# ProPrj_CC-board_2026-02-09.net
KiCad netlist of a schematic drawn in EasyEDA Pro
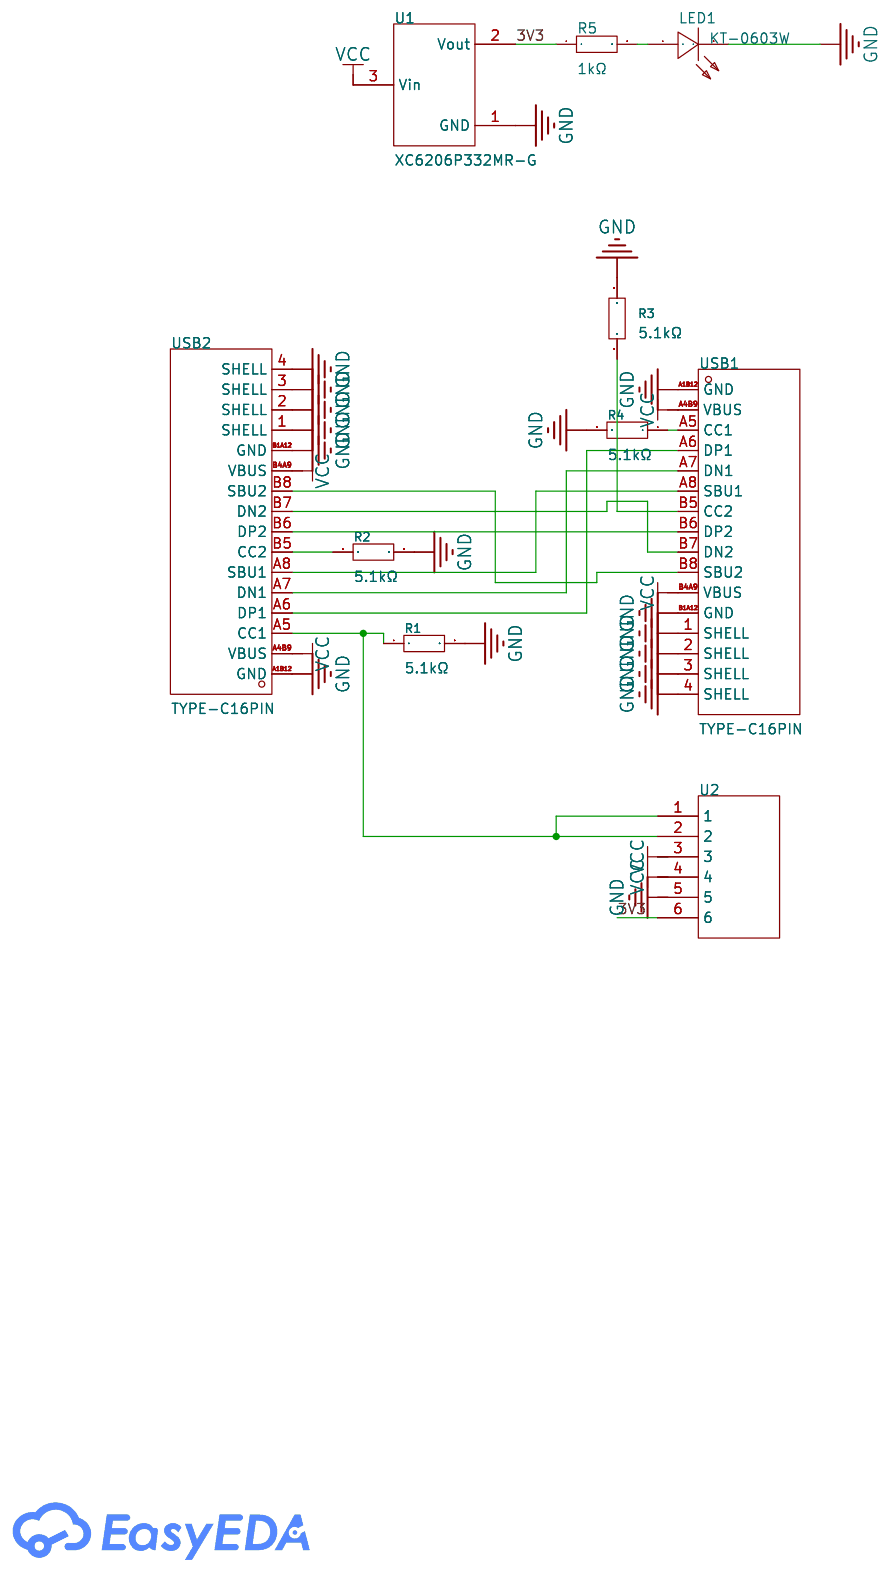
[diagram p0: schematic sheet]

(export (version "E")
  (design (tool "Eeschema 10.0.6"))
  (components
    (comp (ref "LED1")
      (value "KT-0603W")
      (footprint "easyedapro:LED0603-R-RD_WHITE")
      (fields (field (name "Manufacturer") "KENTO"))
      (libsource (lib "easyedapro") (part "0603White light_C2290"))
    )
    (comp (ref "R1")
      (value "5.1kΩ")
      (footprint "easyedapro:R0402")
      (fields
        (field (name "Manufacturer Part") "0402WGF5101TCE")
        (field (name "Manufacturer") "UNI-ROYAL(厚声)")
      )
      (libsource (lib "easyedapro") (part "0402WGF5101TCE"))
    )
    (comp (ref "R2")
      (value "5.1kΩ")
      (footprint "easyedapro:R0402")
      (fields
        (field (name "Manufacturer Part") "0402WGF5101TCE")
        (field (name "Manufacturer") "UNI-ROYAL(厚声)")
      )
      (libsource (lib "easyedapro") (part "0402WGF5101TCE"))
    )
    (comp (ref "R3")
      (value "5.1kΩ")
      (footprint "easyedapro:R0402")
      (fields
        (field (name "Manufacturer Part") "0402WGF5101TCE")
        (field (name "Manufacturer") "UNI-ROYAL(厚声)")
      )
      (libsource (lib "easyedapro") (part "0402WGF5101TCE"))
    )
    (comp (ref "R4")
      (value "5.1kΩ")
      (footprint "easyedapro:R0402")
      (fields
        (field (name "Manufacturer Part") "0402WGF5101TCE")
        (field (name "Manufacturer") "UNI-ROYAL(厚声)")
      )
      (libsource (lib "easyedapro") (part "0402WGF5101TCE"))
    )
    (comp (ref "R5")
      (value "1kΩ")
      (footprint "easyedapro:R0402")
      (fields
        (field (name "Manufacturer Part") "0402WGF1001TCE")
        (field (name "Manufacturer") "UNI-ROYAL(厚声)")
      )
      (libsource (lib "easyedapro") (part "0402WGF1001TCE"))
    )
    (comp (ref "U1")
      (value "XC6206P332MR-G")
      (footprint "easyedapro:SOT-23-3_L2.9-W1.6-P1.90-LS2.8-BR")
      (fields (field (name "Manufacturer") "TOREX(特瑞仕)"))
      (libsource (lib "easyedapro") (part "XC6206P332MR"))
    )
    (comp (ref "U2") (value "~") (footprint "easyedapro:tooth") (libsource (lib "easyedapro") (part "tooth")))
    (comp (ref "USB1")
      (value "TYPE-C16PIN")
      (footprint "easyedapro:USB-C-SMD_TYPE-C16PIN")
      (fields (field (name "Manufacturer") "SHOU HAN(首韩)"))
      (libsource (lib "easyedapro") (part "TYPE-C16PIN"))
    )
    (comp (ref "USB2")
      (value "TYPE-C16PIN")
      (footprint "easyedapro:USB-C-SMD_TYPE-C16PIN")
      (fields (field (name "Manufacturer") "SHOU HAN(首韩)"))
      (libsource (lib "easyedapro") (part "TYPE-C16PIN"))
    )
  )
  (nets
    (net (code "1") (name "/3V3") (class "Default")
      (node (ref "R5") (pin "1") (pinfunction "1_1") (pintype "input"))
      (node (ref "U1") (pin "2") (pinfunction "Vout_2") (pintype "unspecified"))
      (node (ref "U2") (pin "6") (pinfunction "6_6") (pintype "input"))
    )
    (net (code "2") (name "GND") (class "Default")
      (node (ref "LED1") (pin "2") (pinfunction "K_2") (pintype "unspecified"))
      (node (ref "R1") (pin "2") (pinfunction "2_2") (pintype "input"))
      (node (ref "R2") (pin "2") (pinfunction "2_2") (pintype "input"))
      (node (ref "R3") (pin "2") (pinfunction "2_2") (pintype "input"))
      (node (ref "R4") (pin "2") (pinfunction "2_2") (pintype "input"))
      (node (ref "U1") (pin "1") (pinfunction "GND_1") (pintype "unspecified"))
      (node (ref "U2") (pin "5") (pinfunction "5_5") (pintype "input"))
      (node (ref "USB1") (pin "1") (pinfunction "SHELL_1") (pintype "unspecified"))
      (node (ref "USB1") (pin "2") (pinfunction "SHELL_2") (pintype "unspecified"))
      (node (ref "USB1") (pin "3") (pinfunction "SHELL_3") (pintype "unspecified"))
      (node (ref "USB1") (pin "4") (pinfunction "SHELL_4") (pintype "unspecified"))
      (node (ref "USB1") (pin "A1B12") (pinfunction "GND_A1B12") (pintype "unspecified"))
      (node (ref "USB1") (pin "B1A12") (pinfunction "GND_B1A12") (pintype "unspecified"))
      (node (ref "USB2") (pin "1") (pinfunction "SHELL_1") (pintype "unspecified"))
      (node (ref "USB2") (pin "2") (pinfunction "SHELL_2") (pintype "unspecified"))
      (node (ref "USB2") (pin "3") (pinfunction "SHELL_3") (pintype "unspecified"))
      (node (ref "USB2") (pin "4") (pinfunction "SHELL_4") (pintype "unspecified"))
      (node (ref "USB2") (pin "A1B12") (pinfunction "GND_A1B12") (pintype "unspecified"))
      (node (ref "USB2") (pin "B1A12") (pinfunction "GND_B1A12") (pintype "unspecified"))
    )
    (net (code "3") (name "Net-(LED1-A)") (class "Default")
      (node (ref "LED1") (pin "1") (pinfunction "A_1") (pintype "unspecified"))
      (node (ref "R5") (pin "2") (pinfunction "2_2") (pintype "input"))
    )
    (net (code "4") (name "Net-(USB1-CC1)") (class "Default")
      (node (ref "R4") (pin "1") (pinfunction "1_1") (pintype "input"))
      (node (ref "USB1") (pin "A5") (pinfunction "CC1_A5") (pintype "unspecified"))
    )
    (net (code "5") (name "Net-(USB1-CC2)") (class "Default")
      (node (ref "R3") (pin "1") (pinfunction "1_1") (pintype "input"))
      (node (ref "USB1") (pin "B5") (pinfunction "CC2_B5") (pintype "unspecified"))
    )
    (net (code "6") (name "Net-(USB1-DN1)") (class "Default")
      (node (ref "USB1") (pin "A7") (pinfunction "DN1_A7") (pintype "unspecified"))
      (node (ref "USB2") (pin "A7") (pinfunction "DN1_A7") (pintype "unspecified"))
    )
    (net (code "7") (name "Net-(USB1-DN2)") (class "Default")
      (node (ref "USB1") (pin "B7") (pinfunction "DN2_B7") (pintype "unspecified"))
      (node (ref "USB2") (pin "B7") (pinfunction "DN2_B7") (pintype "unspecified"))
    )
    (net (code "8") (name "Net-(USB1-DP1)") (class "Default")
      (node (ref "USB1") (pin "A6") (pinfunction "DP1_A6") (pintype "unspecified"))
      (node (ref "USB2") (pin "A6") (pinfunction "DP1_A6") (pintype "unspecified"))
    )
    (net (code "9") (name "Net-(USB1-DP2)") (class "Default")
      (node (ref "USB1") (pin "B6") (pinfunction "DP2_B6") (pintype "unspecified"))
      (node (ref "USB2") (pin "B6") (pinfunction "DP2_B6") (pintype "unspecified"))
    )
    (net (code "10") (name "Net-(USB1-SBU1)") (class "Default")
      (node (ref "USB1") (pin "A8") (pinfunction "SBU1_A8") (pintype "unspecified"))
      (node (ref "USB2") (pin "A8") (pinfunction "SBU1_A8") (pintype "unspecified"))
    )
    (net (code "11") (name "Net-(USB1-SBU2)") (class "Default")
      (node (ref "USB1") (pin "B8") (pinfunction "SBU2_B8") (pintype "unspecified"))
      (node (ref "USB2") (pin "B8") (pinfunction "SBU2_B8") (pintype "unspecified"))
    )
    (net (code "12") (name "Net-(USB2-CC1)") (class "Default")
      (node (ref "R1") (pin "1") (pinfunction "1_1") (pintype "input"))
      (node (ref "U2") (pin "1") (pinfunction "1_1") (pintype "input"))
      (node (ref "U2") (pin "2") (pinfunction "2_2") (pintype "input"))
      (node (ref "USB2") (pin "A5") (pinfunction "CC1_A5") (pintype "unspecified"))
    )
    (net (code "13") (name "Net-(USB2-CC2)") (class "Default")
      (node (ref "R2") (pin "1") (pinfunction "1_1") (pintype "input"))
      (node (ref "USB2") (pin "B5") (pinfunction "CC2_B5") (pintype "unspecified"))
    )
    (net (code "14") (name "VCC") (class "Default")
      (node (ref "U1") (pin "3") (pinfunction "Vin_3") (pintype "unspecified"))
      (node (ref "U2") (pin "3") (pinfunction "3_3") (pintype "input"))
      (node (ref "U2") (pin "4") (pinfunction "4_4") (pintype "input"))
      (node (ref "USB1") (pin "A4B9") (pinfunction "VBUS_A4B9") (pintype "unspecified"))
      (node (ref "USB1") (pin "B4A9") (pinfunction "VBUS_B4A9") (pintype "unspecified"))
      (node (ref "USB2") (pin "A4B9") (pinfunction "VBUS_A4B9") (pintype "unspecified"))
      (node (ref "USB2") (pin "B4A9") (pinfunction "VBUS_B4A9") (pintype "unspecified"))
    )
  )
)
